# SCH_BotMark_2026-05-25.net
KiCad netlist of a schematic drawn in EasyEDA
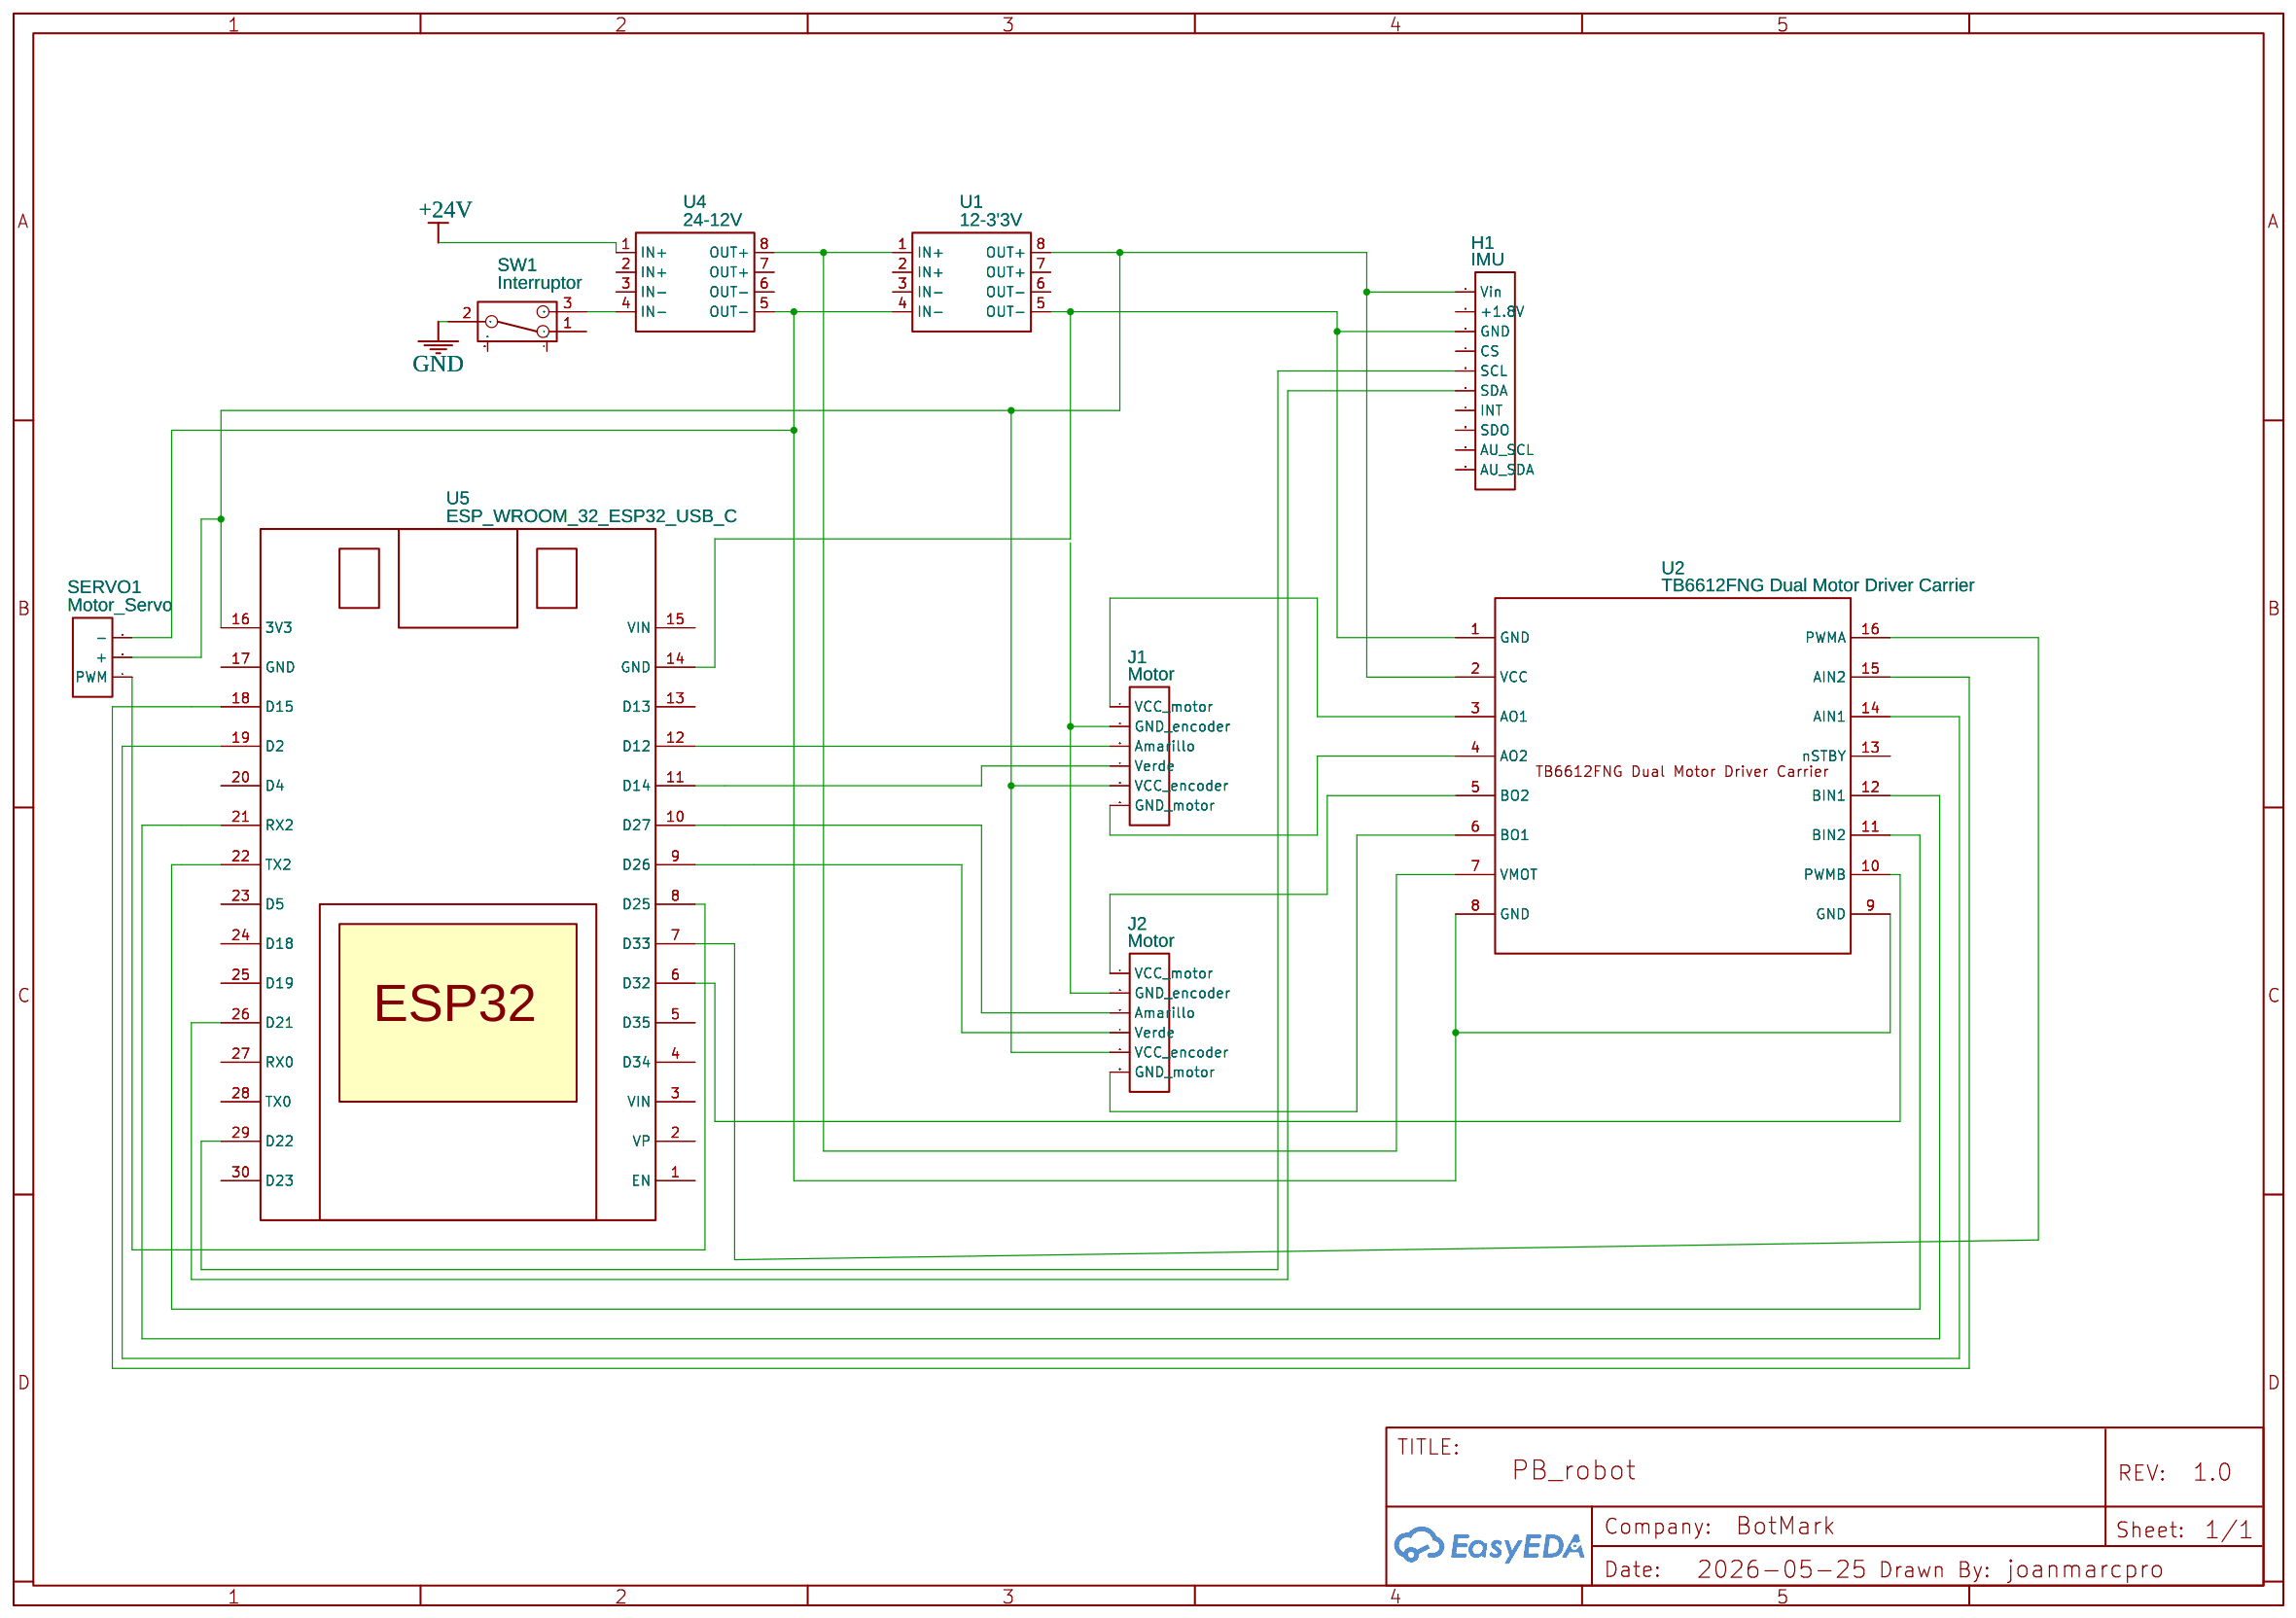
[diagram p0: schematic sheet]

(export (version "E")
  (design (tool "Eeschema 10.0.6"))
  (components
    (comp (ref "H1") (value "IMU") (libsource (lib "") (part "HDR-F-2.54_1x10")))
    (comp (ref "J1") (value "Motor") (libsource (lib "") (part "HDR-M-2.54_1x6")))
    (comp (ref "J2") (value "Motor") (libsource (lib "") (part "HDR-M-2.54_1x6")))
    (comp (ref "SERVO1") (value "Motor_Servo") (libsource (lib "") (part "HDR-M-2.54_1x3")))
    (comp (ref "SW1")
      (value "Interruptor")
      (fields
        (field (name "Manufacturer Part") "SK-12D02-VG5")
        (field (name "Manufacturer") "Rectangular Connectors - Contacts")
      )
      (libsource (lib "") (part "SK-12D02-VG5"))
    )
    (comp (ref "U1")
      (value "12-3'3V")
      (fields (field (name "Manufacturer Part") "MP1584EN_moudle"))
      (libsource (lib "") (part "MP1584EN_MOUDLE"))
    )
    (comp (ref "U2")
      (value "TB6612FNG Dual Motor Driver Carrier")
      (libsource (lib "") (part "TB6612FNG Dual Motor Driver Carrier"))
    )
    (comp (ref "U4")
      (value "24-12V")
      (fields (field (name "Manufacturer Part") "MP1584EN_moudle"))
      (libsource (lib "") (part "MP1584EN_MOUDLE"))
    )
    (comp (ref "U5")
      (value "ESP_WROOM_32_ESP32_USB_C")
      (fields (field (name "Manufacturer Part") "ESP32") (field (name "Manufacturer") "Flutesan"))
      (libsource (lib "") (part "ESP_WROOM_32_ESP32_USB_C"))
    )
  )
  (nets
    (net (code "1") (name "+24V") (class "Default")
      (node (ref "U4") (pin "1") (pinfunction "IN+_1") (pintype "unspecified"))
    )
    (net (code "2") (name "GND") (class "Default")
      (node (ref "SW1") (pin "2") (pinfunction "2_2") (pintype "unspecified"))
    )
    (net (code "3") (name "Net-(H1-GND)") (class "Default")
      (node (ref "H1") (pin "3") (pinfunction "GND_3") (pintype "unspecified"))
      (node (ref "U1") (pin "5") (pinfunction "OUT-_5") (pintype "unspecified"))
      (node (ref "U2") (pin "1") (pinfunction "GND_1") (pintype "unspecified"))
      (node (ref "U5") (pin "14") (pinfunction "GND_14") (pintype "unspecified"))
    )
    (net (code "4") (name "Net-(H1-SCL)") (class "Default")
      (node (ref "H1") (pin "5") (pinfunction "SCL_5") (pintype "unspecified"))
      (node (ref "U5") (pin "29") (pinfunction "D22_29") (pintype "unspecified"))
    )
    (net (code "5") (name "Net-(H1-SDA)") (class "Default")
      (node (ref "H1") (pin "6") (pinfunction "SDA_6") (pintype "unspecified"))
      (node (ref "U5") (pin "26") (pinfunction "D21_26") (pintype "unspecified"))
    )
    (net (code "6") (name "Net-(H1-Vin)") (class "Default")
      (node (ref "H1") (pin "1") (pinfunction "Vin_1") (pintype "unspecified"))
      (node (ref "J1") (pin "5") (pinfunction "VCC_encoder_5") (pintype "input"))
      (node (ref "J2") (pin "5") (pinfunction "VCC_encoder_5") (pintype "input"))
      (node (ref "SERVO1") (pin "2") (pinfunction "+_2") (pintype "input"))
      (node (ref "U1") (pin "8") (pinfunction "OUT+_8") (pintype "unspecified"))
      (node (ref "U2") (pin "2") (pinfunction "VCC_2") (pintype "unspecified"))
      (node (ref "U5") (pin "16") (pinfunction "3V3_16") (pintype "unspecified"))
    )
    (net (code "7") (name "Net-(J1-Amarillo)") (class "Default")
      (node (ref "J1") (pin "3") (pinfunction "Amarillo_3") (pintype "input"))
      (node (ref "U5") (pin "12") (pinfunction "D12_12") (pintype "unspecified"))
    )
    (net (code "8") (name "Net-(J1-GND_encoder)") (class "Default")
      (node (ref "J1") (pin "2") (pinfunction "GND_encoder_2") (pintype "input"))
      (node (ref "J2") (pin "2") (pinfunction "GND_encoder_2") (pintype "input"))
    )
    (net (code "9") (name "Net-(J1-GND_motor)") (class "Default")
      (node (ref "J1") (pin "6") (pinfunction "GND_motor_6") (pintype "input"))
      (node (ref "U2") (pin "4") (pinfunction "AO2_4") (pintype "unspecified"))
    )
    (net (code "10") (name "Net-(J1-VCC_motor)") (class "Default")
      (node (ref "J1") (pin "1") (pinfunction "VCC_motor_1") (pintype "input"))
      (node (ref "U2") (pin "3") (pinfunction "AO1_3") (pintype "unspecified"))
    )
    (net (code "11") (name "Net-(J1-Verde)") (class "Default")
      (node (ref "J1") (pin "4") (pinfunction "Verde_4") (pintype "input"))
      (node (ref "U5") (pin "11") (pinfunction "D14_11") (pintype "unspecified"))
    )
    (net (code "12") (name "Net-(J2-Amarillo)") (class "Default")
      (node (ref "J2") (pin "3") (pinfunction "Amarillo_3") (pintype "input"))
      (node (ref "U5") (pin "10") (pinfunction "D27_10") (pintype "unspecified"))
    )
    (net (code "13") (name "Net-(J2-GND_motor)") (class "Default")
      (node (ref "J2") (pin "6") (pinfunction "GND_motor_6") (pintype "input"))
      (node (ref "U2") (pin "6") (pinfunction "BO1_6") (pintype "unspecified"))
    )
    (net (code "14") (name "Net-(J2-VCC_motor)") (class "Default")
      (node (ref "J2") (pin "1") (pinfunction "VCC_motor_1") (pintype "input"))
      (node (ref "U2") (pin "5") (pinfunction "BO2_5") (pintype "unspecified"))
    )
    (net (code "15") (name "Net-(J2-Verde)") (class "Default")
      (node (ref "J2") (pin "4") (pinfunction "Verde_4") (pintype "input"))
      (node (ref "U5") (pin "9") (pinfunction "D26_9") (pintype "unspecified"))
    )
    (net (code "16") (name "Net-(SERVO1--)") (class "Default")
      (node (ref "SERVO1") (pin "3") (pinfunction "-_3") (pintype "input"))
      (node (ref "U1") (pin "4") (pinfunction "IN-_4") (pintype "unspecified"))
      (node (ref "U2") (pin "8") (pinfunction "GND_8") (pintype "unspecified"))
      (node (ref "U2") (pin "9") (pinfunction "GND_9") (pintype "unspecified"))
      (node (ref "U4") (pin "5") (pinfunction "OUT-_5") (pintype "unspecified"))
    )
    (net (code "17") (name "Net-(SERVO1-PWM)") (class "Default")
      (node (ref "SERVO1") (pin "1") (pinfunction "PWM_1") (pintype "input"))
      (node (ref "U5") (pin "8") (pinfunction "D25_8") (pintype "unspecified"))
    )
    (net (code "18") (name "Net-(SW1-Pad3)") (class "Default")
      (node (ref "SW1") (pin "3") (pinfunction "3_3") (pintype "unspecified"))
      (node (ref "U4") (pin "4") (pinfunction "IN-_4") (pintype "unspecified"))
    )
    (net (code "19") (name "Net-(U2-AIN1)") (class "Default")
      (node (ref "U2") (pin "14") (pinfunction "AIN1_14") (pintype "unspecified"))
      (node (ref "U5") (pin "19") (pinfunction "D2_19") (pintype "unspecified"))
    )
    (net (code "20") (name "Net-(U2-AIN2)") (class "Default")
      (node (ref "U2") (pin "15") (pinfunction "AIN2_15") (pintype "unspecified"))
      (node (ref "U5") (pin "18") (pinfunction "D15_18") (pintype "unspecified"))
    )
    (net (code "21") (name "Net-(U2-BIN1)") (class "Default")
      (node (ref "U2") (pin "12") (pinfunction "BIN1_12") (pintype "unspecified"))
      (node (ref "U5") (pin "21") (pinfunction "RX2_21") (pintype "unspecified"))
    )
    (net (code "22") (name "Net-(U2-BIN2)") (class "Default")
      (node (ref "U2") (pin "11") (pinfunction "BIN2_11") (pintype "unspecified"))
      (node (ref "U5") (pin "22") (pinfunction "TX2_22") (pintype "unspecified"))
    )
    (net (code "23") (name "Net-(U2-PWMA)") (class "Default")
      (node (ref "U2") (pin "16") (pinfunction "PWMA_16") (pintype "unspecified"))
      (node (ref "U5") (pin "7") (pinfunction "D33_7") (pintype "unspecified"))
    )
    (net (code "24") (name "Net-(U2-PWMB)") (class "Default")
      (node (ref "U2") (pin "10") (pinfunction "PWMB_10") (pintype "unspecified"))
      (node (ref "U5") (pin "6") (pinfunction "D32_6") (pintype "unspecified"))
    )
    (net (code "25") (name "Net-(U2-VMOT)") (class "Default")
      (node (ref "U1") (pin "1") (pinfunction "IN+_1") (pintype "unspecified"))
      (node (ref "U2") (pin "7") (pinfunction "VMOT_7") (pintype "unspecified"))
      (node (ref "U4") (pin "8") (pinfunction "OUT+_8") (pintype "unspecified"))
    )
    (net (code "26") (name "unconnected-(H1-+1.8V-Pad2)") (class "Default")
      (node (ref "H1") (pin "2") (pinfunction "+1.8V_2") (pintype "unspecified"))
    )
    (net (code "27") (name "unconnected-(H1-AU_SCL-Pad9)") (class "Default")
      (node (ref "H1") (pin "9") (pinfunction "AU_SCL_9") (pintype "unspecified"))
    )
    (net (code "28") (name "unconnected-(H1-AU_SDA-Pad10)") (class "Default")
      (node (ref "H1") (pin "10") (pinfunction "AU_SDA_10") (pintype "unspecified"))
    )
    (net (code "29") (name "unconnected-(H1-CS-Pad4)") (class "Default")
      (node (ref "H1") (pin "4") (pinfunction "CS_4") (pintype "unspecified"))
    )
    (net (code "30") (name "unconnected-(H1-INT-Pad7)") (class "Default")
      (node (ref "H1") (pin "7") (pinfunction "INT_7") (pintype "unspecified"))
    )
    (net (code "31") (name "unconnected-(H1-SDO-Pad8)") (class "Default")
      (node (ref "H1") (pin "8") (pinfunction "SDO_8") (pintype "unspecified"))
    )
    (net (code "32") (name "unconnected-(SW1-Pad1)") (class "Default")
      (node (ref "SW1") (pin "1") (pinfunction "1_1") (pintype "unspecified"))
    )
    (net (code "33") (name "unconnected-(SW1-Pad4)") (class "Default")
      (node (ref "SW1") (pin "4") (pinfunction "4_4") (pintype "unspecified"))
    )
    (net (code "34") (name "unconnected-(SW1-Pad5)") (class "Default")
      (node (ref "SW1") (pin "5") (pinfunction "5_5") (pintype "unspecified"))
    )
    (net (code "35") (name "unconnected-(U1-IN+-Pad2)") (class "Default")
      (node (ref "U1") (pin "2") (pinfunction "IN+_2") (pintype "unspecified"))
    )
    (net (code "36") (name "unconnected-(U1-IN--Pad3)") (class "Default")
      (node (ref "U1") (pin "3") (pinfunction "IN-_3") (pintype "unspecified"))
    )
    (net (code "37") (name "unconnected-(U1-OUT+-Pad7)") (class "Default")
      (node (ref "U1") (pin "7") (pinfunction "OUT+_7") (pintype "unspecified"))
    )
    (net (code "38") (name "unconnected-(U1-OUT--Pad6)") (class "Default")
      (node (ref "U1") (pin "6") (pinfunction "OUT-_6") (pintype "unspecified"))
    )
    (net (code "39") (name "unconnected-(U2-nSTBY-Pad13)") (class "Default")
      (node (ref "U2") (pin "13") (pinfunction "nSTBY_13") (pintype "unspecified"))
    )
    (net (code "40") (name "unconnected-(U4-IN+-Pad2)") (class "Default")
      (node (ref "U4") (pin "2") (pinfunction "IN+_2") (pintype "unspecified"))
    )
    (net (code "41") (name "unconnected-(U4-IN--Pad3)") (class "Default")
      (node (ref "U4") (pin "3") (pinfunction "IN-_3") (pintype "unspecified"))
    )
    (net (code "42") (name "unconnected-(U4-OUT+-Pad7)") (class "Default")
      (node (ref "U4") (pin "7") (pinfunction "OUT+_7") (pintype "unspecified"))
    )
    (net (code "43") (name "unconnected-(U4-OUT--Pad6)") (class "Default")
      (node (ref "U4") (pin "6") (pinfunction "OUT-_6") (pintype "unspecified"))
    )
    (net (code "44") (name "unconnected-(U5-D4-Pad20)") (class "Default")
      (node (ref "U5") (pin "20") (pinfunction "D4_20") (pintype "unspecified"))
    )
    (net (code "45") (name "unconnected-(U5-D5-Pad23)") (class "Default")
      (node (ref "U5") (pin "23") (pinfunction "D5_23") (pintype "unspecified"))
    )
    (net (code "46") (name "unconnected-(U5-D13-Pad13)") (class "Default")
      (node (ref "U5") (pin "13") (pinfunction "D13_13") (pintype "unspecified"))
    )
    (net (code "47") (name "unconnected-(U5-D18-Pad24)") (class "Default")
      (node (ref "U5") (pin "24") (pinfunction "D18_24") (pintype "unspecified"))
    )
    (net (code "48") (name "unconnected-(U5-D19-Pad25)") (class "Default")
      (node (ref "U5") (pin "25") (pinfunction "D19_25") (pintype "unspecified"))
    )
    (net (code "49") (name "unconnected-(U5-D23-Pad30)") (class "Default")
      (node (ref "U5") (pin "30") (pinfunction "D23_30") (pintype "unspecified"))
    )
    (net (code "50") (name "unconnected-(U5-D34-Pad4)") (class "Default")
      (node (ref "U5") (pin "4") (pinfunction "D34_4") (pintype "unspecified"))
    )
    (net (code "51") (name "unconnected-(U5-D35-Pad5)") (class "Default")
      (node (ref "U5") (pin "5") (pinfunction "D35_5") (pintype "unspecified"))
    )
    (net (code "52") (name "unconnected-(U5-EN-Pad1)") (class "Default")
      (node (ref "U5") (pin "1") (pinfunction "EN_1") (pintype "unspecified"))
    )
    (net (code "53") (name "unconnected-(U5-GND-Pad17)") (class "Default")
      (node (ref "U5") (pin "17") (pinfunction "GND_17") (pintype "unspecified"))
    )
    (net (code "54") (name "unconnected-(U5-RX0-Pad27)") (class "Default")
      (node (ref "U5") (pin "27") (pinfunction "RX0_27") (pintype "unspecified"))
    )
    (net (code "55") (name "unconnected-(U5-TX0-Pad28)") (class "Default")
      (node (ref "U5") (pin "28") (pinfunction "TX0_28") (pintype "unspecified"))
    )
    (net (code "56") (name "unconnected-(U5-VIN-Pad3)") (class "Default")
      (node (ref "U5") (pin "3") (pinfunction "VIN_3") (pintype "unspecified"))
    )
    (net (code "57") (name "unconnected-(U5-VIN-Pad15)") (class "Default")
      (node (ref "U5") (pin "15") (pinfunction "VIN_15") (pintype "unspecified"))
    )
    (net (code "58") (name "unconnected-(U5-VP-Pad2)") (class "Default")
      (node (ref "U5") (pin "2") (pinfunction "VP_2") (pintype "unspecified"))
    )
  )
)
